# SulaMatik.net
KiCad netlist of a schematic drawn in EAGLE
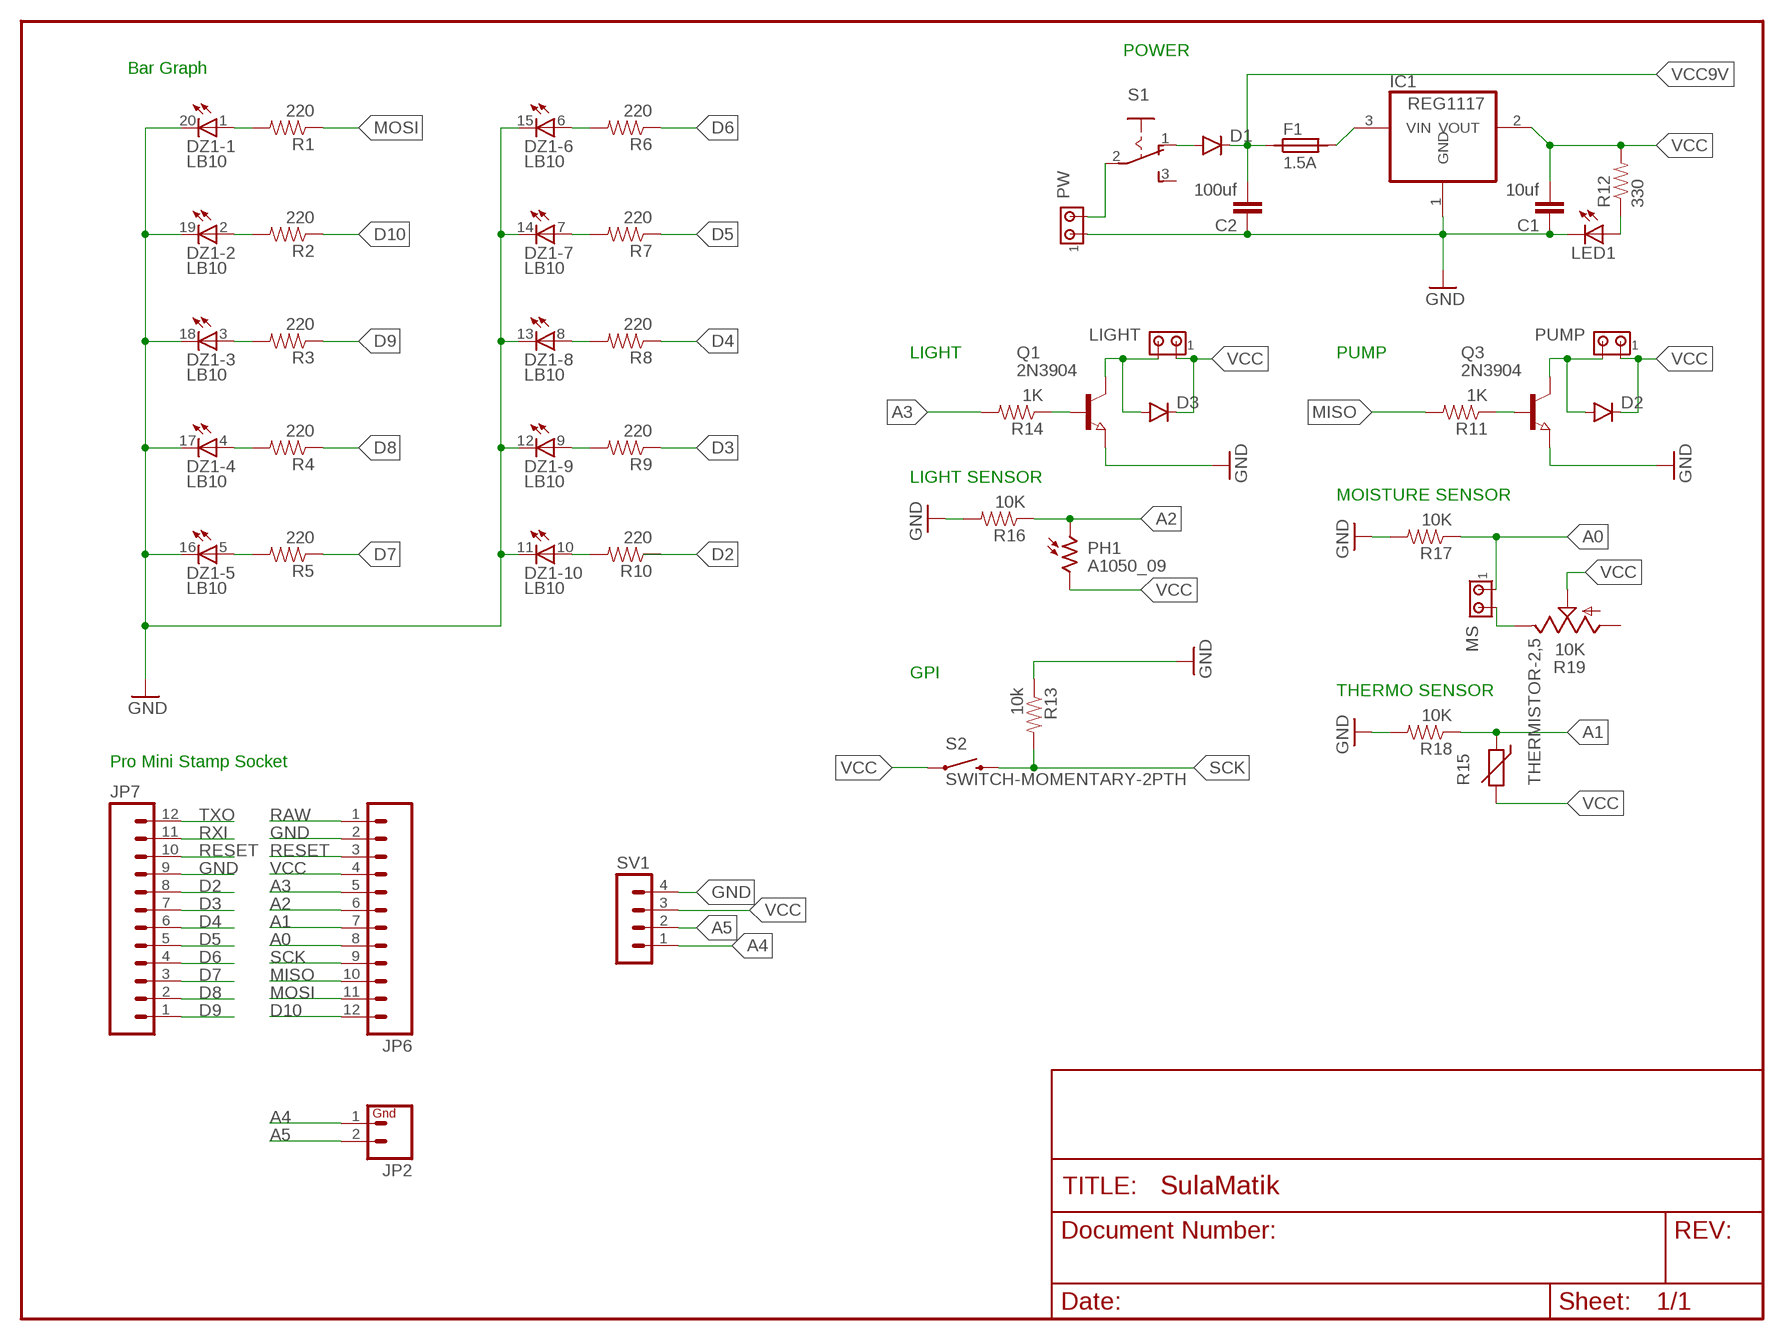
[diagram p0: schematic, sheet 1]

(export (version "E")
  (design (tool "Eeschema 10.0.6"))
  (components
    (comp (ref "C1")
      (value "10uf")
      (footprint "eagle-import:0805")
      (libsource (lib "eagle-import") (part "CAP0805"))
    )
    (comp (ref "C2")
      (value "100uf")
      (footprint "eagle-import:0805")
      (libsource (lib "eagle-import") (part "CAP0805"))
    )
    (comp (ref "D1")
      (value "DIODESMA")
      (footprint "eagle-import:SMA-DIODE")
      (libsource (lib "eagle-import") (part "DIODESMA"))
    )
    (comp (ref "D2")
      (value "DIODESMA")
      (footprint "eagle-import:SMA-DIODE")
      (libsource (lib "eagle-import") (part "DIODESMA"))
    )
    (comp (ref "D3")
      (value "DIODESMA")
      (footprint "eagle-import:SMA-DIODE")
      (libsource (lib "eagle-import") (part "DIODESMA"))
    )
    (comp (ref "DZ1")
      (value "LB10")
      (footprint "eagle-import:LB10")
      (libsource (lib "eagle-import") (part "LB10"))
    )
    (comp (ref "F1")
      (value "1.5A")
      (footprint "eagle-import:1820")
      (libsource (lib "eagle-import") (part "SIBA194600"))
    )
    (comp (ref "IC1")
      (value "REG1117")
      (footprint "eagle-import:SOT223")
      (libsource (lib "eagle-import") (part "REG1117"))
    )
    (comp (ref "JP2")
      (value "M02PTH")
      (footprint "eagle-import:1X02")
      (libsource (lib "eagle-import") (part "M02PTH"))
    )
    (comp (ref "JP6")
      (value "M12PTH")
      (footprint "eagle-import:1X12")
      (libsource (lib "eagle-import") (part "M12PTH"))
    )
    (comp (ref "JP7")
      (value "M12PTH")
      (footprint "eagle-import:1X12")
      (libsource (lib "eagle-import") (part "M12PTH"))
    )
    (comp (ref "LED1")
      (value "LEDCHIP-LED0805")
      (footprint "eagle-import:CHIP-LED0805")
      (libsource (lib "eagle-import") (part "LEDCHIP-LED0805"))
    )
    (comp (ref "LIGHT")
      (value "MTA02-156")
      (footprint "eagle-import:1X2MTA")
      (libsource (lib "eagle-import") (part "MTA02-156"))
    )
    (comp (ref "MS")
      (value "MTA02-156")
      (footprint "eagle-import:1X2MTA")
      (libsource (lib "eagle-import") (part "MTA02-156"))
    )
    (comp (ref "PH1")
      (value "A1050_09")
      (footprint "eagle-import:T0-46-A10XX")
      (libsource (lib "eagle-import") (part "A1050_09"))
    )
    (comp (ref "PUMP")
      (value "MTA02-156")
      (footprint "eagle-import:1X2MTA")
      (libsource (lib "eagle-import") (part "MTA02-156"))
    )
    (comp (ref "PW")
      (value "MTA02-156")
      (footprint "eagle-import:1X2MTA")
      (libsource (lib "eagle-import") (part "MTA02-156"))
    )
    (comp (ref "Q1")
      (value "2N3904")
      (footprint "eagle-import:SOT23")
      (libsource (lib "eagle-import") (part "NPN-TRANSISTOR_SOT23"))
    )
    (comp (ref "Q3")
      (value "2N3904")
      (footprint "eagle-import:SOT23")
      (libsource (lib "eagle-import") (part "NPN-TRANSISTOR_SOT23"))
    )
    (comp (ref "R1")
      (value "220")
      (footprint "eagle-import:0805")
      (libsource (lib "eagle-import") (part "RESISTOR0805-RES"))
    )
    (comp (ref "R2")
      (value "220")
      (footprint "eagle-import:0805")
      (libsource (lib "eagle-import") (part "RESISTOR0805-RES"))
    )
    (comp (ref "R3")
      (value "220")
      (footprint "eagle-import:0805")
      (libsource (lib "eagle-import") (part "RESISTOR0805-RES"))
    )
    (comp (ref "R4")
      (value "220")
      (footprint "eagle-import:0805")
      (libsource (lib "eagle-import") (part "RESISTOR0805-RES"))
    )
    (comp (ref "R5")
      (value "220")
      (footprint "eagle-import:0805")
      (libsource (lib "eagle-import") (part "RESISTOR0805-RES"))
    )
    (comp (ref "R6")
      (value "220")
      (footprint "eagle-import:0805")
      (libsource (lib "eagle-import") (part "RESISTOR0805-RES"))
    )
    (comp (ref "R7")
      (value "220")
      (footprint "eagle-import:0805")
      (libsource (lib "eagle-import") (part "RESISTOR0805-RES"))
    )
    (comp (ref "R8")
      (value "220")
      (footprint "eagle-import:0805")
      (libsource (lib "eagle-import") (part "RESISTOR0805-RES"))
    )
    (comp (ref "R9")
      (value "220")
      (footprint "eagle-import:0805")
      (libsource (lib "eagle-import") (part "RESISTOR0805-RES"))
    )
    (comp (ref "R10")
      (value "220")
      (footprint "eagle-import:0805")
      (libsource (lib "eagle-import") (part "RESISTOR0805-RES"))
    )
    (comp (ref "R11")
      (value "1K")
      (footprint "eagle-import:0805")
      (libsource (lib "eagle-import") (part "RESISTOR0805-RES"))
    )
    (comp (ref "R12")
      (value "330")
      (footprint "eagle-import:0805")
      (libsource (lib "eagle-import") (part "RESISTOR0805-RES"))
    )
    (comp (ref "R13")
      (value "10k")
      (footprint "eagle-import:0805")
      (libsource (lib "eagle-import") (part "RESISTOR0805-RES"))
    )
    (comp (ref "R14")
      (value "1K")
      (footprint "eagle-import:0805")
      (libsource (lib "eagle-import") (part "RESISTOR0805-RES"))
    )
    (comp (ref "R15")
      (value "THERMISTOR-2,5")
      (footprint "eagle-import:RS-2,5")
      (libsource (lib "eagle-import") (part "THERMISTOR-2,5"))
    )
    (comp (ref "R16")
      (value "10K")
      (footprint "eagle-import:0805")
      (libsource (lib "eagle-import") (part "RESISTOR0805-RES"))
    )
    (comp (ref "R17")
      (value "10K")
      (footprint "eagle-import:0805")
      (libsource (lib "eagle-import") (part "RESISTOR0805-RES"))
    )
    (comp (ref "R18")
      (value "10K")
      (footprint "eagle-import:0805")
      (libsource (lib "eagle-import") (part "RESISTOR0805-RES"))
    )
    (comp (ref "R19")
      (value "10K")
      (footprint "eagle-import:CA6V")
      (libsource (lib "eagle-import") (part "TRIM_US-CA6V"))
    )
    (comp (ref "S1")
      (value "255SB")
      (footprint "eagle-import:255SB")
      (libsource (lib "eagle-import") (part "255SB"))
    )
    (comp (ref "S2")
      (value "SWITCH-MOMENTARY-2PTH")
      (footprint "eagle-import:TACTILE-PTH")
      (libsource (lib "eagle-import") (part "SWITCH-MOMENTARY-2PTH"))
    )
    (comp (ref "SV1")
      (value "MA04-1")
      (footprint "eagle-import:MA04-1")
      (libsource (lib "eagle-import") (part "MA04-1"))
    )
  )
  (nets
    (net (code "1") (name "/RAW") (class "Default")
      (node (ref "JP6") (pin "1") (pinfunction "1_1") (pintype "passive"))
    )
    (net (code "2") (name "/RESET") (class "Default")
      (node (ref "JP6") (pin "3") (pinfunction "3_3") (pintype "passive"))
      (node (ref "JP7") (pin "10") (pinfunction "10_10") (pintype "passive"))
    )
    (net (code "3") (name "/RXI") (class "Default")
      (node (ref "JP7") (pin "11") (pinfunction "11_11") (pintype "passive"))
    )
    (net (code "4") (name "/TXO") (class "Default")
      (node (ref "JP7") (pin "12") (pinfunction "12_12") (pintype "passive"))
    )
    (net (code "5") (name "A0") (class "Default")
      (node (ref "JP6") (pin "8") (pinfunction "8_8") (pintype "passive"))
      (node (ref "MS") (pin "1") (pinfunction "1_1") (pintype "passive"))
      (node (ref "R17") (pin "1") (pinfunction "1_1") (pintype "passive"))
    )
    (net (code "6") (name "A1") (class "Default")
      (node (ref "JP6") (pin "7") (pinfunction "7_7") (pintype "passive"))
      (node (ref "R15") (pin "1") (pinfunction "1_1") (pintype "passive"))
      (node (ref "R18") (pin "1") (pinfunction "1_1") (pintype "passive"))
    )
    (net (code "7") (name "A2") (class "Default")
      (node (ref "JP6") (pin "6") (pinfunction "6_6") (pintype "passive"))
      (node (ref "PH1") (pin "1") (pinfunction "1_1") (pintype "passive"))
      (node (ref "R16") (pin "1") (pinfunction "1_1") (pintype "passive"))
    )
    (net (code "8") (name "A3") (class "Default")
      (node (ref "JP6") (pin "5") (pinfunction "5_5") (pintype "passive"))
      (node (ref "R14") (pin "2") (pinfunction "2_2") (pintype "passive"))
    )
    (net (code "9") (name "A4") (class "Default")
      (node (ref "JP2") (pin "1") (pinfunction "1_1") (pintype "passive"))
      (node (ref "SV1") (pin "1") (pinfunction "1_1") (pintype "passive"))
    )
    (net (code "10") (name "A5") (class "Default")
      (node (ref "JP2") (pin "2") (pinfunction "2_2") (pintype "passive"))
      (node (ref "SV1") (pin "2") (pinfunction "2_2") (pintype "passive"))
    )
    (net (code "11") (name "D2") (class "Default")
      (node (ref "JP7") (pin "8") (pinfunction "8_8") (pintype "passive"))
      (node (ref "R10") (pin "1") (pinfunction "1_1") (pintype "passive"))
    )
    (net (code "12") (name "D3") (class "Default")
      (node (ref "JP7") (pin "7") (pinfunction "7_7") (pintype "passive"))
      (node (ref "R9") (pin "1") (pinfunction "1_1") (pintype "passive"))
    )
    (net (code "13") (name "D4") (class "Default")
      (node (ref "JP7") (pin "6") (pinfunction "6_6") (pintype "passive"))
      (node (ref "R8") (pin "1") (pinfunction "1_1") (pintype "passive"))
    )
    (net (code "14") (name "D5") (class "Default")
      (node (ref "JP7") (pin "5") (pinfunction "5_5") (pintype "passive"))
      (node (ref "R7") (pin "1") (pinfunction "1_1") (pintype "passive"))
    )
    (net (code "15") (name "D6") (class "Default")
      (node (ref "JP7") (pin "4") (pinfunction "4_4") (pintype "passive"))
      (node (ref "R6") (pin "1") (pinfunction "1_1") (pintype "passive"))
    )
    (net (code "16") (name "D7") (class "Default")
      (node (ref "JP7") (pin "3") (pinfunction "3_3") (pintype "passive"))
      (node (ref "R5") (pin "1") (pinfunction "1_1") (pintype "passive"))
    )
    (net (code "17") (name "D8") (class "Default")
      (node (ref "JP7") (pin "2") (pinfunction "2_2") (pintype "passive"))
      (node (ref "R4") (pin "1") (pinfunction "1_1") (pintype "passive"))
    )
    (net (code "18") (name "D9") (class "Default")
      (node (ref "JP7") (pin "1") (pinfunction "1_1") (pintype "passive"))
      (node (ref "R3") (pin "1") (pinfunction "1_1") (pintype "passive"))
    )
    (net (code "19") (name "D10") (class "Default")
      (node (ref "JP6") (pin "12") (pinfunction "12_12") (pintype "passive"))
      (node (ref "R2") (pin "1") (pinfunction "1_1") (pintype "passive"))
    )
    (net (code "20") (name "GND") (class "Default")
      (node (ref "C1") (pin "1") (pinfunction "1_1") (pintype "passive"))
      (node (ref "C2") (pin "1") (pinfunction "1_1") (pintype "passive"))
      (node (ref "DZ1") (pin "11") (pinfunction "C_11") (pintype "passive"))
      (node (ref "DZ1") (pin "12") (pinfunction "C_12") (pintype "passive"))
      (node (ref "DZ1") (pin "13") (pinfunction "C_13") (pintype "passive"))
      (node (ref "DZ1") (pin "14") (pinfunction "C_14") (pintype "passive"))
      (node (ref "DZ1") (pin "15") (pinfunction "C_15") (pintype "passive"))
      (node (ref "DZ1") (pin "16") (pinfunction "C_16") (pintype "passive"))
      (node (ref "DZ1") (pin "17") (pinfunction "C_17") (pintype "passive"))
      (node (ref "DZ1") (pin "18") (pinfunction "C_18") (pintype "passive"))
      (node (ref "DZ1") (pin "19") (pinfunction "C_19") (pintype "passive"))
      (node (ref "DZ1") (pin "20") (pinfunction "C_20") (pintype "passive"))
      (node (ref "IC1") (pin "1") (pinfunction "GND_1") (pintype "power_in"))
      (node (ref "JP6") (pin "2") (pinfunction "2_2") (pintype "passive"))
      (node (ref "JP7") (pin "9") (pinfunction "9_9") (pintype "passive"))
      (node (ref "LED1") (pin "C") (pinfunction "C_C") (pintype "passive"))
      (node (ref "PW") (pin "1") (pinfunction "1_1") (pintype "passive"))
      (node (ref "Q1") (pin "2") (pinfunction "E_2") (pintype "passive"))
      (node (ref "Q3") (pin "2") (pinfunction "E_2") (pintype "passive"))
      (node (ref "R13") (pin "1") (pinfunction "1_1") (pintype "passive"))
      (node (ref "R16") (pin "2") (pinfunction "2_2") (pintype "passive"))
      (node (ref "R17") (pin "2") (pinfunction "2_2") (pintype "passive"))
      (node (ref "R18") (pin "2") (pinfunction "2_2") (pintype "passive"))
      (node (ref "SV1") (pin "4") (pinfunction "4_4") (pintype "passive"))
    )
    (net (code "21") (name "MISO") (class "Default")
      (node (ref "JP6") (pin "10") (pinfunction "10_10") (pintype "passive"))
      (node (ref "R11") (pin "2") (pinfunction "2_2") (pintype "passive"))
    )
    (net (code "22") (name "MOSI") (class "Default")
      (node (ref "JP6") (pin "11") (pinfunction "11_11") (pintype "passive"))
      (node (ref "R1") (pin "1") (pinfunction "1_1") (pintype "passive"))
    )
    (net (code "23") (name "Net-(DZ1A-A)") (class "Default")
      (node (ref "DZ1") (pin "1") (pinfunction "A_1") (pintype "passive"))
      (node (ref "R1") (pin "2") (pinfunction "2_2") (pintype "passive"))
    )
    (net (code "24") (name "Net-(DZ1B-A)") (class "Default")
      (node (ref "DZ1") (pin "10") (pinfunction "A_10") (pintype "passive"))
      (node (ref "R10") (pin "2") (pinfunction "2_2") (pintype "passive"))
    )
    (net (code "25") (name "Net-(DZ1C-A)") (class "Default")
      (node (ref "DZ1") (pin "2") (pinfunction "A_2") (pintype "passive"))
      (node (ref "R2") (pin "2") (pinfunction "2_2") (pintype "passive"))
    )
    (net (code "26") (name "Net-(DZ1D-A)") (class "Default")
      (node (ref "DZ1") (pin "3") (pinfunction "A_3") (pintype "passive"))
      (node (ref "R3") (pin "2") (pinfunction "2_2") (pintype "passive"))
    )
    (net (code "27") (name "Net-(DZ1E-A)") (class "Default")
      (node (ref "DZ1") (pin "4") (pinfunction "A_4") (pintype "passive"))
      (node (ref "R4") (pin "2") (pinfunction "2_2") (pintype "passive"))
    )
    (net (code "28") (name "Net-(DZ1F-A)") (class "Default")
      (node (ref "DZ1") (pin "5") (pinfunction "A_5") (pintype "passive"))
      (node (ref "R5") (pin "2") (pinfunction "2_2") (pintype "passive"))
    )
    (net (code "29") (name "Net-(DZ1G-A)") (class "Default")
      (node (ref "DZ1") (pin "6") (pinfunction "A_6") (pintype "passive"))
      (node (ref "R6") (pin "2") (pinfunction "2_2") (pintype "passive"))
    )
    (net (code "30") (name "Net-(DZ1H-A)") (class "Default")
      (node (ref "DZ1") (pin "7") (pinfunction "A_7") (pintype "passive"))
      (node (ref "R7") (pin "2") (pinfunction "2_2") (pintype "passive"))
    )
    (net (code "31") (name "Net-(DZ1I-A)") (class "Default")
      (node (ref "DZ1") (pin "8") (pinfunction "A_8") (pintype "passive"))
      (node (ref "R8") (pin "2") (pinfunction "2_2") (pintype "passive"))
    )
    (net (code "32") (name "Net-(DZ1J-A)") (class "Default")
      (node (ref "DZ1") (pin "9") (pinfunction "A_9") (pintype "passive"))
      (node (ref "R9") (pin "2") (pinfunction "2_2") (pintype "passive"))
    )
    (net (code "33") (name "Net-(IC1-VIN)") (class "Default")
      (node (ref "F1") (pin "2") (pinfunction "2_2") (pintype "passive"))
      (node (ref "IC1") (pin "3") (pinfunction "VIN_3") (pintype "input"))
    )
    (net (code "34") (name "Net-(LED1-PadA)") (class "Default")
      (node (ref "LED1") (pin "A") (pinfunction "A_A") (pintype "passive"))
      (node (ref "R12") (pin "1") (pinfunction "1_1") (pintype "passive"))
    )
    (net (code "35") (name "Net-(MS-Pad2)") (class "Default")
      (node (ref "MS") (pin "2") (pinfunction "2_2") (pintype "passive"))
      (node (ref "R19") (pin "E") (pinfunction "E_E") (pintype "passive"))
    )
    (net (code "36") (name "Net-(Q1-B)") (class "Default")
      (node (ref "Q1") (pin "1") (pinfunction "B_1") (pintype "passive"))
      (node (ref "R14") (pin "1") (pinfunction "1_1") (pintype "passive"))
    )
    (net (code "37") (name "Net-(Q1-C)") (class "Default")
      (node (ref "D3") (pin "A") (pinfunction "A_A") (pintype "passive"))
      (node (ref "LIGHT") (pin "2") (pinfunction "2_2") (pintype "passive"))
      (node (ref "Q1") (pin "3") (pinfunction "C_3") (pintype "passive"))
    )
    (net (code "38") (name "Net-(Q3-B)") (class "Default")
      (node (ref "Q3") (pin "1") (pinfunction "B_1") (pintype "passive"))
      (node (ref "R11") (pin "1") (pinfunction "1_1") (pintype "passive"))
    )
    (net (code "39") (name "Net-(Q3-C)") (class "Default")
      (node (ref "D2") (pin "A") (pinfunction "A_A") (pintype "passive"))
      (node (ref "PUMP") (pin "2") (pinfunction "2_2") (pintype "passive"))
      (node (ref "Q3") (pin "3") (pinfunction "C_3") (pintype "passive"))
    )
    (net (code "40") (name "Net-(S1-O)") (class "Default")
      (node (ref "D1") (pin "A") (pinfunction "A_A") (pintype "passive"))
      (node (ref "S1") (pin "1") (pinfunction "O_1") (pintype "passive"))
    )
    (net (code "41") (name "Net-(S1-P)") (class "Default")
      (node (ref "PW") (pin "2") (pinfunction "2_2") (pintype "passive"))
      (node (ref "S1") (pin "2") (pinfunction "P_2") (pintype "passive"))
    )
    (net (code "42") (name "SCK") (class "Default")
      (node (ref "JP6") (pin "9") (pinfunction "9_9") (pintype "passive"))
      (node (ref "R13") (pin "2") (pinfunction "2_2") (pintype "passive"))
      (node (ref "S2") (pin "3") (pinfunction "2_3") (pintype "passive"))
    )
    (net (code "43") (name "VCC") (class "Default")
      (node (ref "C1") (pin "2") (pinfunction "2_2") (pintype "passive"))
      (node (ref "D2") (pin "C") (pinfunction "C_C") (pintype "passive"))
      (node (ref "D3") (pin "C") (pinfunction "C_C") (pintype "passive"))
      (node (ref "IC1") (pin "2") (pinfunction "VOUT_2") (pintype "output"))
      (node (ref "JP6") (pin "4") (pinfunction "4_4") (pintype "passive"))
      (node (ref "LIGHT") (pin "1") (pinfunction "1_1") (pintype "passive"))
      (node (ref "PH1") (pin "2") (pinfunction "2_2") (pintype "passive"))
      (node (ref "PUMP") (pin "1") (pinfunction "1_1") (pintype "passive"))
      (node (ref "R12") (pin "2") (pinfunction "2_2") (pintype "passive"))
      (node (ref "R15") (pin "2") (pinfunction "2_2") (pintype "passive"))
      (node (ref "R19") (pin "S") (pinfunction "S_S") (pintype "passive"))
      (node (ref "S2") (pin "1") (pinfunction "1_1") (pintype "passive"))
      (node (ref "SV1") (pin "3") (pinfunction "3_3") (pintype "passive"))
    )
    (net (code "44") (name "VCC9V") (class "Default")
      (node (ref "C2") (pin "2") (pinfunction "2_2") (pintype "passive"))
      (node (ref "D1") (pin "C") (pinfunction "C_C") (pintype "passive"))
      (node (ref "F1") (pin "1") (pinfunction "1_1") (pintype "passive"))
    )
    (net (code "45") (name "unconnected-(R19-PadA)") (class "Default")
      (node (ref "R19") (pin "A") (pinfunction "A_A") (pintype "passive"))
    )
    (net (code "46") (name "unconnected-(S1-S-Pad3)") (class "Default")
      (node (ref "S1") (pin "3") (pinfunction "S_3") (pintype "passive"))
    )
  )
)
